# USBasp.net
KiCad netlist of a schematic drawn in Altium Designer
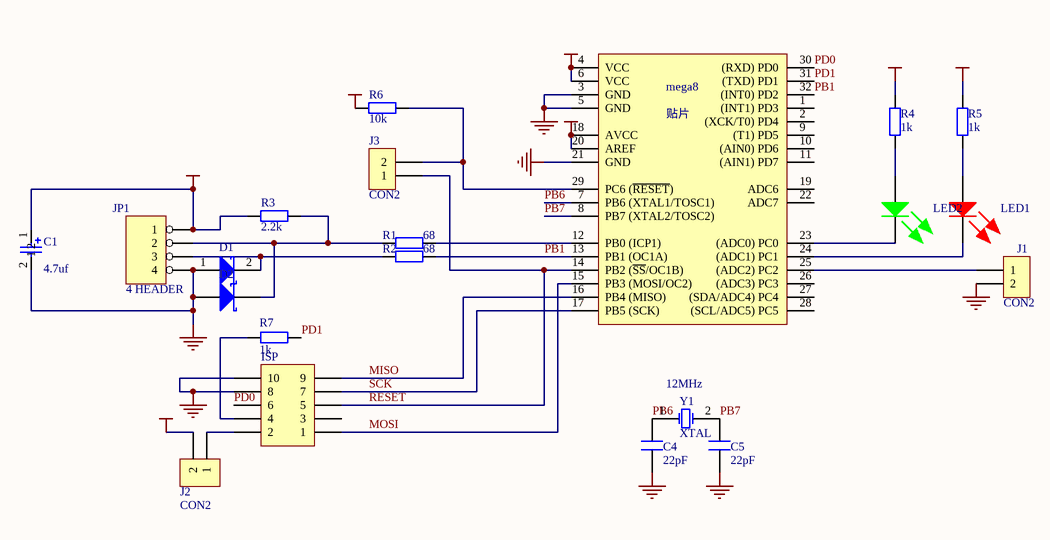
[diagram p0: USBasp_下载线.SchDoc]

(export (version "E")
  (design (tool "Eeschema 10.0.6"))
  (components
    (comp (ref "C1")
      (value "4.7uf")
      (footprint "TPDR")
      (description "Polarized Capacitor (Axial)")
      (fields (field (name "PUBLISHER") "Altium Limited"))
      (libsource (lib "Miscellaneous Devices") (part "Cap Pol2"))
    )
    (comp (ref "C4")
      (value "22pF")
      (footprint "TP-0805-R")
      (description "Capacitor SMD1206")
      (libsource (lib "*") (part "CAPSMD"))
    )
    (comp (ref "C5")
      (value "22pF")
      (footprint "TP-0805-R")
      (description "Capacitor SMD1206")
      (libsource (lib "*") (part "CAPSMD"))
    )
    (comp (ref "D1")
      (value "Diode 11DQ03")
      (footprint "TPDR")
      (description "Schottky Rectifier")
      (fields (field (name "PUBLISHER") "Altium Limited"))
      (libsource (lib "Miscellaneous Devices") (part "Diode 11DQ03"))
    )
    (comp (ref "D2")
      (value "Diode 11DQ03")
      (footprint "TPDR")
      (description "Schottky Rectifier")
      (fields (field (name "PUBLISHER") "Altium Limited"))
      (libsource (lib "") (part "Diode 11DQ03_1"))
    )
    (comp (ref "ISP")
      (value "~")
      (footprint "HDR2X5")
      (description "Header, 5-Pin, Dual row, Right Angle")
      (fields (field (name "MANUFACTURER") "Generic Components"))
      (libsource (lib "*") (part "MLW10A"))
    )
    (comp (ref "J1")
      (value "CON2")
      (footprint "HDR1X2")
      (description "Connector")
      (libsource (lib "") (part "CON2_2"))
    )
    (comp (ref "J2")
      (value "CON2")
      (footprint "HDR1X2")
      (description "Connector")
      (libsource (lib "") (part "CON2_1"))
    )
    (comp (ref "J3")
      (value "CON2")
      (footprint "HDR1X2")
      (description "Connector")
      (libsource (lib "*") (part "CON2"))
    )
    (comp (ref "JP1")
      (value "4 HEADER")
      (footprint "USB-5V")
      (description "4 Pin Header")
      (libsource (lib "*") (part "4 HEADER"))
    )
    (comp (ref "LED1")
      (value "~")
      (footprint "TP-0805-D")
      (description "Piros Led 3mm")
      (libsource (lib "*") (part "LED Piros"))
    )
    (comp (ref "LED2")
      (value "~")
      (footprint "TP-0805-D")
      (description "Zöld Led 3mm")
      (libsource (lib "*") (part "LED Zöld"))
    )
    (comp (ref "mega8")
      (value "贴片")
      (footprint "QFP7x7-G32/N")
      (description "8 位微处理器/32引脚")
      (fields (field (name "发布者") "磊元工作室"))
      (libsource (lib "微控制处理器") (part "ATmega8-A"))
    )
    (comp (ref "R1")
      (value "68")
      (footprint "TP-0805-R")
      (description "Resistor SMD1206, 1% fémréteg")
      (libsource (lib "*") (part "RES"))
    )
    (comp (ref "R2")
      (value "68")
      (footprint "TP-0805-R")
      (description "Resistor SMD1206, 1% fémréteg")
      (libsource (lib "*") (part "RES"))
    )
    (comp (ref "R3")
      (value "2.2k")
      (footprint "TP-0805-R")
      (description "Resistor SMD1206, 1% fémréteg")
      (libsource (lib "*") (part "RES"))
    )
    (comp (ref "R4")
      (value "1k")
      (footprint "TP-0805-R")
      (description "Resistor SMD1206, 1% fémréteg")
      (libsource (lib "*") (part "RES"))
    )
    (comp (ref "R5")
      (value "1k")
      (footprint "TP-0805-R")
      (description "Resistor SMD1206, 1% fémréteg")
      (libsource (lib "*") (part "RES"))
    )
    (comp (ref "R6")
      (value "10k")
      (footprint "TP-0805-R")
      (description "Resistor SMD1206, 1% fémréteg")
      (libsource (lib "*") (part "RES"))
    )
    (comp (ref "R7")
      (value "1k")
      (footprint "TP-0805-R")
      (description "Resistor SMD1206, 1% fémréteg")
      (libsource (lib "*") (part "RES"))
    )
    (comp (ref "Y1")
      (value "XTAL")
      (footprint "JZ_ZC")
      (description "Crystal Oscillator")
      (fields
        (field (name "MANUFACTURER") "Generic Components")
        (field (name "ALTIUM_VALUE") "12MHz")
        (field (name "PUBLISHER") "Altium Hobart Technology Centre")
      )
      (libsource (lib "*") (part "XTAL"))
    )
  )
  (nets
    (net (code "1") (name "/MISO") (class "Default")
      (node (ref "ISP") (pin "9") (pinfunction "9_9") (pintype "passive"))
      (node (ref "mega8") (pin "16") (pinfunction "PB4_(MISO)_16") (pintype "passive"))
    )
    (net (code "2") (name "/MOSI") (class "Default")
      (node (ref "ISP") (pin "1") (pinfunction "1_1") (pintype "passive"))
      (node (ref "mega8") (pin "15") (pinfunction "PB3_(MOSI/OC2)_15") (pintype "passive"))
    )
    (net (code "3") (name "/PB1") (class "Default")
      (node (ref "R2") (pin "1") (pinfunction "1_1") (pintype "passive"))
      (node (ref "mega8") (pin "13") (pinfunction "PB1_(OC1A)_13") (pintype "passive"))
      (node (ref "mega8") (pin "32") (pinfunction "(INT0)_PD2_32") (pintype "passive"))
    )
    (net (code "4") (name "/PB6") (class "Default")
      (node (ref "C4") (pin "2") (pinfunction "2_2") (pintype "passive"))
      (node (ref "Y1") (pin "1") (pinfunction "OSC1_1") (pintype "passive"))
      (node (ref "mega8") (pin "7") (pinfunction "PB6_(XTAL1/TOSC1)_7") (pintype "passive"))
    )
    (net (code "5") (name "/PB7") (class "Default")
      (node (ref "C5") (pin "2") (pinfunction "2_2") (pintype "passive"))
      (node (ref "Y1") (pin "2") (pinfunction "OSC2_2") (pintype "passive"))
      (node (ref "mega8") (pin "8") (pinfunction "PB7_(XTAL2/TOSC2)_8") (pintype "passive"))
    )
    (net (code "6") (name "/PD0") (class "Default")
      (node (ref "ISP") (pin "6") (pinfunction "6_6") (pintype "passive"))
      (node (ref "mega8") (pin "30") (pinfunction "(RXD)_PD0_30") (pintype "passive"))
    )
    (net (code "7") (name "/PD1") (class "Default")
      (node (ref "R7") (pin "2") (pinfunction "2_2") (pintype "passive"))
      (node (ref "mega8") (pin "31") (pinfunction "(TXD)_PD1_31") (pintype "passive"))
    )
    (net (code "8") (name "/RESET") (class "Default")
      (node (ref "ISP") (pin "5") (pinfunction "5_5") (pintype "passive"))
      (node (ref "J3") (pin "1") (pinfunction "1_1") (pintype "passive"))
      (node (ref "mega8") (pin "14") (pinfunction "PB2_(~{SS}/OC1B)_14") (pintype "passive"))
    )
    (net (code "9") (name "/SCK") (class "Default")
      (node (ref "ISP") (pin "7") (pinfunction "7_7") (pintype "passive"))
      (node (ref "mega8") (pin "17") (pinfunction "PB5_(SCK)_17") (pintype "passive"))
    )
    (net (code "10") (name "GND") (class "Default")
      (node (ref "C1") (pin "2") (pinfunction "2_2") (pintype "passive"))
      (node (ref "C4") (pin "1") (pinfunction "1_1") (pintype "passive"))
      (node (ref "C5") (pin "1") (pinfunction "1_1") (pintype "passive"))
      (node (ref "D1") (pin "1") (pinfunction "A_1") (pintype "passive"))
      (node (ref "D2") (pin "1") (pinfunction "A_1") (pintype "passive"))
      (node (ref "ISP") (pin "10") (pinfunction "10_10") (pintype "passive"))
      (node (ref "ISP") (pin "8") (pinfunction "8_8") (pintype "passive"))
      (node (ref "J1") (pin "2") (pinfunction "2_2") (pintype "passive"))
      (node (ref "JP1") (pin "4") (pinfunction "4_4") (pintype "passive"))
      (node (ref "mega8") (pin "21") (pinfunction "GND_21") (pintype "passive"))
      (node (ref "mega8") (pin "3") (pinfunction "GND_3") (pintype "passive"))
      (node (ref "mega8") (pin "5") (pinfunction "GND_5") (pintype "passive"))
    )
    (net (code "11") (name "Net-(D1-K)") (class "Default")
      (node (ref "D1") (pin "2") (pinfunction "K_2") (pintype "passive"))
      (node (ref "JP1") (pin "3") (pinfunction "3_3") (pintype "passive"))
      (node (ref "R2") (pin "2") (pinfunction "2_2") (pintype "passive"))
    )
    (net (code "12") (name "Net-(D2-K)") (class "Default")
      (node (ref "D2") (pin "2") (pinfunction "K_2") (pintype "passive"))
      (node (ref "JP1") (pin "2") (pinfunction "2_2") (pintype "passive"))
      (node (ref "R1") (pin "1") (pinfunction "1_1") (pintype "passive"))
      (node (ref "R3") (pin "1") (pinfunction "1_1") (pintype "passive"))
    )
    (net (code "13") (name "Net-(ISP-Pad2)") (class "Default")
      (node (ref "ISP") (pin "2") (pinfunction "2_2") (pintype "passive"))
      (node (ref "J2") (pin "1") (pinfunction "1_1") (pintype "passive"))
    )
    (net (code "14") (name "Net-(ISP-Pad4)") (class "Default")
      (node (ref "ISP") (pin "4") (pinfunction "4_4") (pintype "passive"))
      (node (ref "R7") (pin "1") (pinfunction "1_1") (pintype "passive"))
    )
    (net (code "15") (name "Net-(LED1-Pad1)") (class "Default")
      (node (ref "LED1") (pin "1") (pinfunction "1_1") (pintype "passive"))
      (node (ref "R5") (pin "1") (pinfunction "1_1") (pintype "passive"))
    )
    (net (code "16") (name "Net-(LED2-Pad1)") (class "Default")
      (node (ref "LED2") (pin "1") (pinfunction "1_1") (pintype "passive"))
      (node (ref "R4") (pin "1") (pinfunction "1_1") (pintype "passive"))
    )
    (net (code "17") (name "Net-(mega8-(ADC0)_PC0)") (class "Default")
      (node (ref "LED2") (pin "2") (pinfunction "2_2") (pintype "passive"))
      (node (ref "mega8") (pin "23") (pinfunction "(ADC0)_PC0_23") (pintype "passive"))
    )
    (net (code "18") (name "Net-(mega8-(ADC1)_PC1)") (class "Default")
      (node (ref "LED1") (pin "2") (pinfunction "2_2") (pintype "passive"))
      (node (ref "mega8") (pin "24") (pinfunction "(ADC1)_PC1_24") (pintype "passive"))
    )
    (net (code "19") (name "Net-(mega8-(ADC2)_PC2)") (class "Default")
      (node (ref "J1") (pin "1") (pinfunction "1_1") (pintype "passive"))
      (node (ref "mega8") (pin "25") (pinfunction "(ADC2)_PC2_25") (pintype "passive"))
    )
    (net (code "20") (name "Net-(mega8-PB0_(ICP1))") (class "Default")
      (node (ref "R1") (pin "2") (pinfunction "2_2") (pintype "passive"))
      (node (ref "mega8") (pin "12") (pinfunction "PB0_(ICP1)_12") (pintype "passive"))
    )
    (net (code "21") (name "Net-(mega8-PC6_(~{RESET}))") (class "Default")
      (node (ref "J3") (pin "2") (pinfunction "2_2") (pintype "passive"))
      (node (ref "R6") (pin "1") (pinfunction "1_1") (pintype "passive"))
      (node (ref "mega8") (pin "29") (pinfunction "PC6_(~{RESET})_29") (pintype "passive"))
    )
    (net (code "22") (name "VCC") (class "Default")
      (node (ref "C1") (pin "1") (pinfunction "1_1") (pintype "passive"))
      (node (ref "J2") (pin "2") (pinfunction "2_2") (pintype "passive"))
      (node (ref "JP1") (pin "1") (pinfunction "1_1") (pintype "passive"))
      (node (ref "R3") (pin "2") (pinfunction "2_2") (pintype "passive"))
      (node (ref "R4") (pin "2") (pinfunction "2_2") (pintype "passive"))
      (node (ref "R5") (pin "2") (pinfunction "2_2") (pintype "passive"))
      (node (ref "R6") (pin "2") (pinfunction "2_2") (pintype "passive"))
      (node (ref "mega8") (pin "18") (pinfunction "AVCC_18") (pintype "passive"))
      (node (ref "mega8") (pin "20") (pinfunction "AREF_20") (pintype "passive"))
      (node (ref "mega8") (pin "4") (pinfunction "VCC_4") (pintype "passive"))
      (node (ref "mega8") (pin "6") (pinfunction "VCC_6") (pintype "passive"))
    )
    (net (code "23") (name "unconnected-(ISP-Pad3)") (class "Default")
      (node (ref "ISP") (pin "3") (pinfunction "3_3") (pintype "passive"))
    )
    (net (code "24") (name "unconnected-(mega8-(ADC3)_PC3-Pad26)") (class "Default")
      (node (ref "mega8") (pin "26") (pinfunction "(ADC3)_PC3_26") (pintype "passive"))
    )
    (net (code "25") (name "unconnected-(mega8-(AIN0)_PD6-Pad10)") (class "Default")
      (node (ref "mega8") (pin "10") (pinfunction "(AIN0)_PD6_10") (pintype "passive"))
    )
    (net (code "26") (name "unconnected-(mega8-(AIN1)_PD7-Pad11)") (class "Default")
      (node (ref "mega8") (pin "11") (pinfunction "(AIN1)_PD7_11") (pintype "passive"))
    )
    (net (code "27") (name "unconnected-(mega8-(INT1)_PD3-Pad1)") (class "Default")
      (node (ref "mega8") (pin "1") (pinfunction "(INT1)_PD3_1") (pintype "passive"))
    )
    (net (code "28") (name "unconnected-(mega8-(SCL{slash}ADC5)_PC5-Pad28)") (class "Default")
      (node (ref "mega8") (pin "28") (pinfunction "(SCL/ADC5)_PC5_28") (pintype "passive"))
    )
    (net (code "29") (name "unconnected-(mega8-(SDA{slash}ADC4)_PC4-Pad27)") (class "Default")
      (node (ref "mega8") (pin "27") (pinfunction "(SDA/ADC4)_PC4_27") (pintype "passive"))
    )
    (net (code "30") (name "unconnected-(mega8-(T1)_PD5-Pad9)") (class "Default")
      (node (ref "mega8") (pin "9") (pinfunction "(T1)_PD5_9") (pintype "passive"))
    )
    (net (code "31") (name "unconnected-(mega8-(XCK{slash}T0)_PD4-Pad2)") (class "Default")
      (node (ref "mega8") (pin "2") (pinfunction "(XCK/T0)_PD4_2") (pintype "passive"))
    )
    (net (code "32") (name "unconnected-(mega8-ADC6-Pad19)") (class "Default")
      (node (ref "mega8") (pin "19") (pinfunction "ADC6_19") (pintype "passive"))
    )
    (net (code "33") (name "unconnected-(mega8-ADC7-Pad22)") (class "Default")
      (node (ref "mega8") (pin "22") (pinfunction "ADC7_22") (pintype "passive"))
    )
  )
)
